# STM8S103_FM1702.net
KiCad netlist of a schematic drawn in Altium Designer
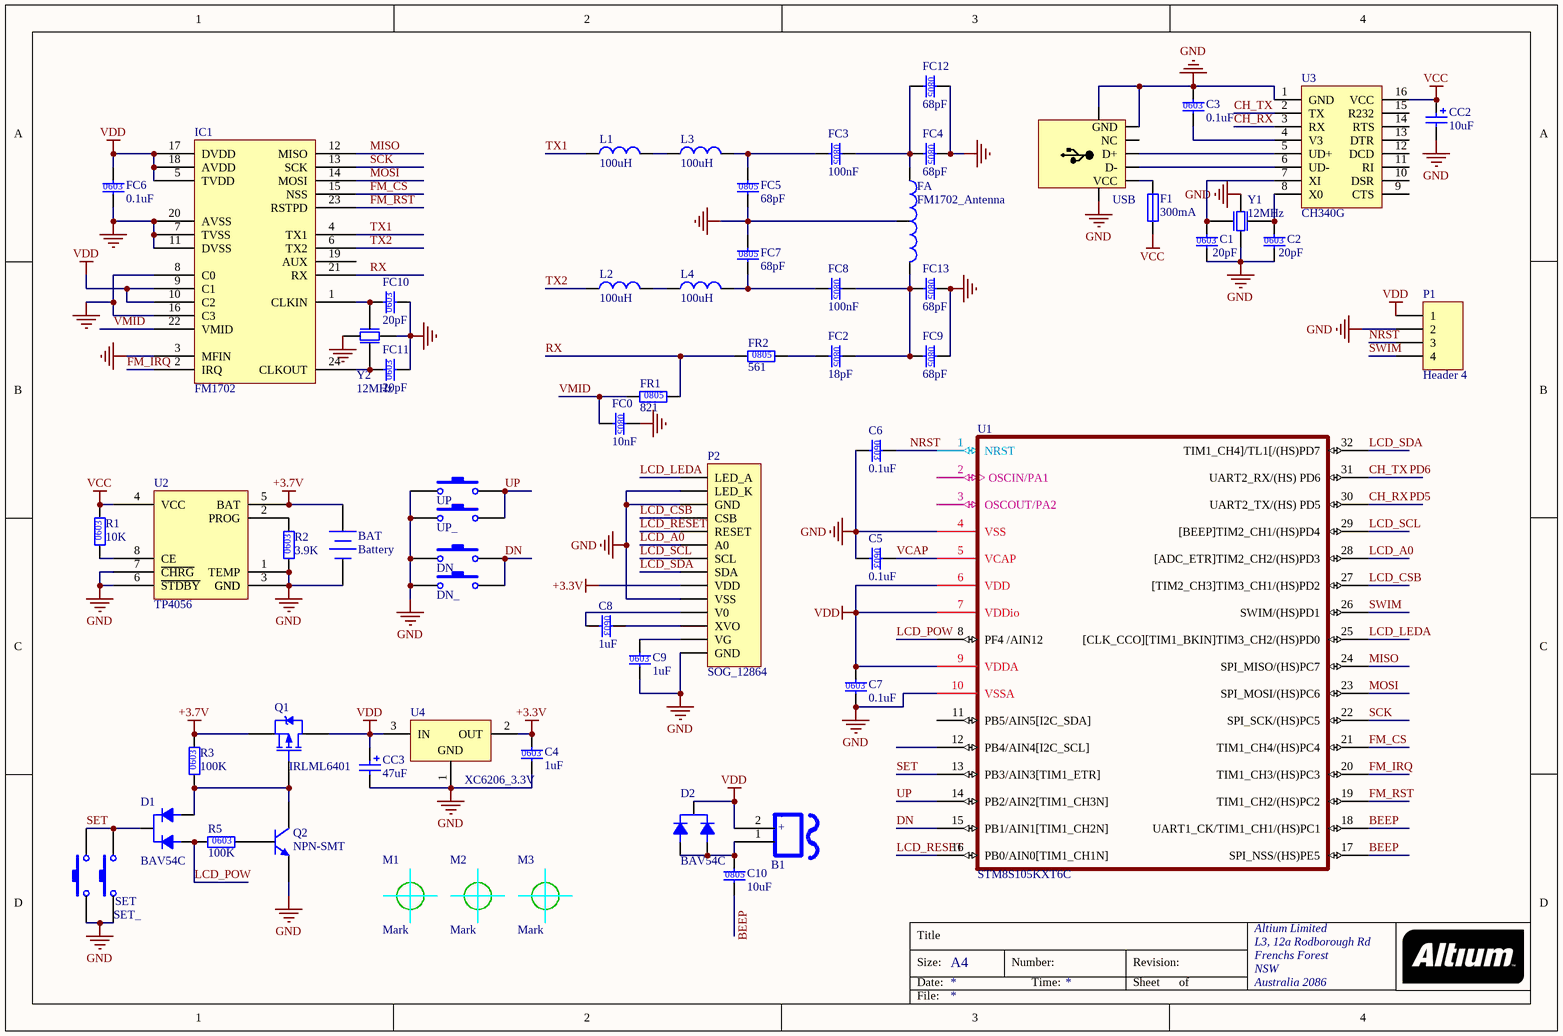
[diagram p0: STM8S103_FM1702.SchDoc]

(export (version "E")
  (design (tool "Eeschema 10.0.6"))
  (components
    (comp (ref "B1")
      (value "BUZZER")
      (footprint "BUZZ_9025")
      (libsource (lib "EButterflySchmeticLibrary") (part "BUZZER"))
    )
    (comp (ref "BAT")
      (value "Battery")
      (footprint "HX1.25-2")
      (description "Multicell Battery")
      (fields (field (name "PUBLISHER") "Altium Limited"))
      (libsource (lib "Altium Designer") (part "Battery-N"))
    )
    (comp (ref "C1")
      (value "20pF")
      (footprint "C0603")
      (description "Polarized Capacitor (Radial)")
      (fields (field (name "Comment") "C0603") (field (name "PUBLISHER") "Altium Limited"))
      (libsource (lib "Capacitance") (part "C0603"))
    )
    (comp (ref "C2")
      (value "20pF")
      (footprint "C0603")
      (description "Polarized Capacitor (Radial)")
      (fields (field (name "Comment") "C0603") (field (name "PUBLISHER") "Altium Limited"))
      (libsource (lib "Capacitance") (part "C0603"))
    )
    (comp (ref "C3")
      (value "0.1uF")
      (footprint "C0603")
      (description "Polarized Capacitor (Radial)")
      (fields (field (name "Comment") "C0603") (field (name "PUBLISHER") "Altium Limited"))
      (libsource (lib "Capacitance") (part "C0603"))
    )
    (comp (ref "C4")
      (value "1uF")
      (footprint "C0603")
      (description "Polarized Capacitor (Radial)")
      (fields (field (name "Comment") "C0603") (field (name "PUBLISHER") "Altium Limited"))
      (libsource (lib "Capacitance") (part "C0603"))
    )
    (comp (ref "C5")
      (value "0.1uF")
      (footprint "C0603")
      (description "Polarized Capacitor (Radial)")
      (fields (field (name "Comment") "C0603") (field (name "PUBLISHER") "Altium Limited"))
      (libsource (lib "Capacitance") (part "C0603"))
    )
    (comp (ref "C6")
      (value "0.1uF")
      (footprint "C0603")
      (description "Polarized Capacitor (Radial)")
      (fields (field (name "Comment") "C0603") (field (name "PUBLISHER") "Altium Limited"))
      (libsource (lib "Capacitance") (part "C0603"))
    )
    (comp (ref "C7")
      (value "0.1uF")
      (footprint "C0603")
      (description "Polarized Capacitor (Radial)")
      (fields (field (name "Comment") "C0603") (field (name "PUBLISHER") "Altium Limited"))
      (libsource (lib "Capacitance") (part "C0603"))
    )
    (comp (ref "C8")
      (value "1uF")
      (footprint "C0603")
      (description "Polarized Capacitor (Radial)")
      (fields (field (name "Comment") "C0603") (field (name "PUBLISHER") "Altium Limited"))
      (libsource (lib "Capacitance") (part "C0603"))
    )
    (comp (ref "C9")
      (value "1uF")
      (footprint "C0603")
      (description "Polarized Capacitor (Radial)")
      (fields (field (name "Comment") "C0603") (field (name "PUBLISHER") "Altium Limited"))
      (libsource (lib "Capacitance") (part "C0603"))
    )
    (comp (ref "C10")
      (value "10uF")
      (footprint "C0805")
      (description "Polarized Capacitor (Radial)")
      (fields (field (name "Comment") "C0805") (field (name "PUBLISHER") "Altium Limited"))
      (libsource (lib "Capacitance") (part "C0805"))
    )
    (comp (ref "CC2")
      (value "Cap Tan B")
      (footprint "TAN-B-3528")
      (description "Polarized Capacitor (Radial)")
      (fields
        (field (name "CAPACITANCE") "10uF")
        (field (name "VOLTAGE") "16V")
        (field (name "PUBLISHER") "Altium Limited")
      )
      (libsource (lib "Capacitance") (part "Cap Tan B"))
    )
    (comp (ref "CC3")
      (value "Cap Tan C")
      (footprint "TAN-C-6032")
      (description "Polarized Capacitor (Radial)")
      (fields
        (field (name "CAPACITANCE") "47uF")
        (field (name "VOLTAGE") "10V")
        (field (name "PUBLISHER") "Altium Limited")
      )
      (libsource (lib "Capacitance") (part "Cap Tan C"))
    )
    (comp (ref "D1")
      (value "BAS40_5")
      (footprint "SOT-23")
      (description "Default Diode")
      (fields (field (name "ALTIUM_UNNAMED_1") "BAV54C") (field (name "PUBLISHER") "Altium Limited"))
      (libsource (lib "Diode") (part "BAS40_5"))
    )
    (comp (ref "D2")
      (value "BAS40_5")
      (footprint "SOT-23")
      (description "Default Diode")
      (fields (field (name "ALTIUM_UNNAMED_1") "BAV54C") (field (name "PUBLISHER") "Altium Limited"))
      (libsource (lib "Diode") (part "BAS40_5"))
    )
    (comp (ref "DN")
      (value "Button")
      (footprint "BUTTON_SMD")
      (fields (field (name "PUBLISHER") "Altium Limited"))
      (libsource (lib "EButterflySchmeticLibrary") (part "Button"))
    )
    (comp (ref "DN_")
      (value "Button")
      (footprint "SWITCH_SMD")
      (fields (field (name "PUBLISHER") "Altium Limited"))
      (libsource (lib "EButterflySchmeticLibrary") (part "Button"))
    )
    (comp (ref "F1")
      (value "300mA")
      (footprint "F1206")
      (description "Fuse")
      (fields (field (name "PUBLISHER") "Altium Limited"))
      (libsource (lib "EButterflySchmeticLibrary") (part "Fuse"))
    )
    (comp (ref "FA")
      (value "FM1702_Antenna")
      (footprint "FM1702_Antenna")
      (libsource (lib "STM8S103_FM1702") (part "FM1702_Antenna"))
    )
    (comp (ref "FC0")
      (value "10nF")
      (footprint "C0805")
      (description "Polarized Capacitor (Radial)")
      (fields (field (name "Comment") "C0805") (field (name "PUBLISHER") "Altium Limited"))
      (libsource (lib "Capacitance") (part "C0805"))
    )
    (comp (ref "FC2")
      (value "18pF")
      (footprint "C0805")
      (description "Polarized Capacitor (Radial)")
      (fields (field (name "Comment") "C0805") (field (name "PUBLISHER") "Altium Limited"))
      (libsource (lib "Capacitance") (part "C0805"))
    )
    (comp (ref "FC3")
      (value "100nF")
      (footprint "C0805")
      (description "Polarized Capacitor (Radial)")
      (fields (field (name "Comment") "C0805") (field (name "PUBLISHER") "Altium Limited"))
      (libsource (lib "Capacitance") (part "C0805"))
    )
    (comp (ref "FC4")
      (value "68pF")
      (footprint "C0805")
      (description "Polarized Capacitor (Radial)")
      (fields (field (name "Comment") "C0805") (field (name "PUBLISHER") "Altium Limited"))
      (libsource (lib "Capacitance") (part "C0805"))
    )
    (comp (ref "FC5")
      (value "68pF")
      (footprint "C0805")
      (description "Polarized Capacitor (Radial)")
      (fields (field (name "Comment") "C0805") (field (name "PUBLISHER") "Altium Limited"))
      (libsource (lib "Capacitance") (part "C0805"))
    )
    (comp (ref "FC6")
      (value "0.1uF")
      (footprint "C0603")
      (description "Polarized Capacitor (Radial)")
      (fields (field (name "Comment") "C0603") (field (name "PUBLISHER") "Altium Limited"))
      (libsource (lib "Capacitance") (part "C0603"))
    )
    (comp (ref "FC7")
      (value "68pF")
      (footprint "C0805")
      (description "Polarized Capacitor (Radial)")
      (fields (field (name "Comment") "C0805") (field (name "PUBLISHER") "Altium Limited"))
      (libsource (lib "Capacitance") (part "C0805"))
    )
    (comp (ref "FC8")
      (value "100nF")
      (footprint "C0805")
      (description "Polarized Capacitor (Radial)")
      (fields (field (name "Comment") "C0805") (field (name "PUBLISHER") "Altium Limited"))
      (libsource (lib "Capacitance") (part "C0805"))
    )
    (comp (ref "FC9")
      (value "68pF")
      (footprint "C0805")
      (description "Polarized Capacitor (Radial)")
      (fields (field (name "Comment") "C0805") (field (name "PUBLISHER") "Altium Limited"))
      (libsource (lib "Capacitance") (part "C0805"))
    )
    (comp (ref "FC10")
      (value "20pF")
      (footprint "C0603")
      (description "Polarized Capacitor (Radial)")
      (fields (field (name "Comment") "C0603") (field (name "PUBLISHER") "Altium Limited"))
      (libsource (lib "Capacitance") (part "C0603"))
    )
    (comp (ref "FC11")
      (value "20pF")
      (footprint "C0603")
      (description "Polarized Capacitor (Radial)")
      (fields (field (name "Comment") "C0603") (field (name "PUBLISHER") "Altium Limited"))
      (libsource (lib "Capacitance") (part "C0603"))
    )
    (comp (ref "FC12")
      (value "68pF")
      (footprint "C0805")
      (description "Polarized Capacitor (Radial)")
      (fields (field (name "Comment") "C0805") (field (name "PUBLISHER") "Altium Limited"))
      (libsource (lib "Capacitance") (part "C0805"))
    )
    (comp (ref "FC13")
      (value "68pF")
      (footprint "C0805")
      (description "Polarized Capacitor (Radial)")
      (fields (field (name "Comment") "C0805") (field (name "PUBLISHER") "Altium Limited"))
      (libsource (lib "Capacitance") (part "C0805"))
    )
    (comp (ref "FR1")
      (value "?")
      (footprint "R0805")
      (fields (field (name "ALTIUM_UNNAMED_1") "821"))
      (libsource (lib "Resistor") (part "R0805"))
    )
    (comp (ref "FR2")
      (value "?")
      (footprint "R0805")
      (fields (field (name "ALTIUM_UNNAMED_1") "561"))
      (libsource (lib "Resistor") (part "R0805"))
    )
    (comp (ref "IC1") (value "FM1702") (footprint "SOP-24L") (libsource (lib "MixedICs") (part "FM1702")))
    (comp (ref "L1")
      (value "100uH")
      (footprint "L2013-0805")
      (description "Inductor")
      (fields (field (name "Comment") "Inductor Chip") (field (name "PUBLISHER") "Altium Limited"))
      (libsource (lib "EButterflySchmeticLibrary") (part "Inductor Chip"))
    )
    (comp (ref "L2")
      (value "100uH")
      (footprint "L2013-0805")
      (description "Inductor")
      (fields (field (name "Comment") "Inductor Chip") (field (name "PUBLISHER") "Altium Limited"))
      (libsource (lib "EButterflySchmeticLibrary") (part "Inductor Chip"))
    )
    (comp (ref "L3")
      (value "100uH")
      (footprint "L2013-0805")
      (description "Inductor")
      (fields (field (name "Comment") "Inductor Chip") (field (name "PUBLISHER") "Altium Limited"))
      (libsource (lib "EButterflySchmeticLibrary") (part "Inductor Chip"))
    )
    (comp (ref "L4")
      (value "100uH")
      (footprint "L2013-0805")
      (description "Inductor")
      (fields (field (name "Comment") "Inductor Chip") (field (name "PUBLISHER") "Altium Limited"))
      (libsource (lib "EButterflySchmeticLibrary") (part "Inductor Chip"))
    )
    (comp (ref "M1")
      (value "Mark")
      (footprint "MARK")
      (fields (field (name "PUBLISHER") "Altium Limited"))
      (libsource (lib "EButterflySchmeticLibrary") (part "Mark"))
    )
    (comp (ref "M2")
      (value "Mark")
      (footprint "MARK")
      (fields (field (name "PUBLISHER") "Altium Limited"))
      (libsource (lib "EButterflySchmeticLibrary") (part "Mark"))
    )
    (comp (ref "M3")
      (value "Mark")
      (footprint "MARK")
      (fields (field (name "PUBLISHER") "Altium Limited"))
      (libsource (lib "EButterflySchmeticLibrary") (part "Mark"))
    )
    (comp (ref "P1")
      (value "Header 4")
      (footprint "HDR1X4")
      (description "Header, 4-Pin")
      (fields (field (name "PUBLISHER") "Altium Limited"))
      (libsource (lib "Connectors") (part "Header 4"))
    )
    (comp (ref "P2")
      (value "SOG_12864")
      (footprint "SOG12864")
      (fields (field (name "PUBLISHER") "Altium Limited"))
      (libsource (lib "Optoelectronic") (part "SOG_12864"))
    )
    (comp (ref "Q1")
      (value "IRLML6401")
      (footprint "SOT-23")
      (description "P-Channel Power MOSFET")
      (fields (field (name "PUBLISHER") "Altium Limited"))
      (libsource (lib "EButterflySchmeticLibrary") (part "IRLML6401"))
    )
    (comp (ref "Q2")
      (value "NPN-SMT")
      (footprint "SO-G3/C2.5")
      (description "NPN Bipolar Transistor")
      (fields (field (name "PUBLISHER") "Altium Limited"))
      (libsource (lib "EButterflySchmeticLibrary") (part "NPN-SMT"))
    )
    (comp (ref "R1")
      (value "?")
      (footprint "R0603")
      (fields (field (name "ALTIUM_UNNAMED_1") "10K"))
      (libsource (lib "Resistor") (part "R0603"))
    )
    (comp (ref "R2")
      (value "?")
      (footprint "R0603")
      (fields (field (name "ALTIUM_UNNAMED_1") "3.9K"))
      (libsource (lib "Resistor") (part "R0603"))
    )
    (comp (ref "R3")
      (value "?")
      (footprint "R0603")
      (fields (field (name "ALTIUM_UNNAMED_1") "100K"))
      (libsource (lib "Resistor") (part "R0603"))
    )
    (comp (ref "R5")
      (value "?")
      (footprint "R0603")
      (fields (field (name "ALTIUM_UNNAMED_1") "100K"))
      (libsource (lib "") (part "R0603_1"))
    )
    (comp (ref "SET")
      (value "Button")
      (footprint "BUTTON_SMD")
      (fields (field (name "PUBLISHER") "Altium Limited"))
      (libsource (lib "EButterflySchmeticLibrary") (part "Button"))
    )
    (comp (ref "SET_")
      (value "Button")
      (footprint "SWITCH_SMD")
      (fields (field (name "PUBLISHER") "Altium Limited"))
      (libsource (lib "EButterflySchmeticLibrary") (part "Button"))
    )
    (comp (ref "U1")
      (value "STM8S105KXT6C")
      (footprint "TQFP-32AN")
      (description "ST 8-bit  Microcontroller")
      (libsource (lib "STM8S") (part "STM8S105K4T6C"))
    )
    (comp (ref "U2") (value "TP4056") (footprint "SOP-8PAD") (libsource (lib "PowerICs") (part "TP4056")))
    (comp (ref "U3") (value "CH340G") (footprint "SOP-16L") (libsource (lib "MixedICs") (part "CH340G")))
    (comp (ref "U4")
      (value "XC6206_3.3V")
      (footprint "SOT-23")
      (description "POSITIVE OUTPUT VOLTAGE")
      (libsource (lib "PowerICs") (part "XC6206"))
    )
    (comp (ref "UP")
      (value "Button")
      (footprint "BUTTON_SMD")
      (fields (field (name "PUBLISHER") "Altium Limited"))
      (libsource (lib "EButterflySchmeticLibrary") (part "Button"))
    )
    (comp (ref "UP_")
      (value "Button")
      (footprint "SWITCH_SMD")
      (fields (field (name "PUBLISHER") "Altium Limited"))
      (libsource (lib "EButterflySchmeticLibrary") (part "Button"))
    )
    (comp (ref "USB") (value "USB") (footprint "USB-B_Micro") (libsource (lib "Connectors") (part "USB")))
    (comp (ref "Y1")
      (value "CRYSTAL")
      (footprint "X3225")
      (description "Crystal Oscillator")
      (fields (field (name "FREQUENCY") "12MHz") (field (name "PUBLISHER") "Altium Limited"))
      (libsource (lib "EButterflySchmeticLibrary") (part "CRYSTAL"))
    )
    (comp (ref "Y2")
      (value "CRYSTAL")
      (footprint "X3225")
      (description "Crystal Oscillator")
      (fields (field (name "FREQUENCY") "12MHz") (field (name "PUBLISHER") "Altium Limited"))
      (libsource (lib "EButterflySchmeticLibrary") (part "CRYSTAL"))
    )
  )
  (nets
    (net (code "1") (name "+3.3V") (class "Default")
      (node (ref "C4") (pin "1") (pinfunction "1_1") (pintype "passive"))
      (node (ref "P2") (pin "9") (pinfunction "VDD_9") (pintype "passive"))
      (node (ref "U4") (pin "2") (pinfunction "OUT_2") (pintype "power_in"))
    )
    (net (code "2") (name "+3.7V") (class "Default")
      (node (ref "BAT") (pin "2") (pinfunction "+_2") (pintype "passive"))
      (node (ref "Q1") (pin "2") (pinfunction "S_2") (pintype "passive"))
      (node (ref "R3") (pin "2") (pinfunction "2_2") (pintype "passive"))
      (node (ref "U2") (pin "5") (pinfunction "BAT_5") (pintype "passive"))
    )
    (net (code "3") (name "/BEEP") (class "Default")
      (node (ref "C10") (pin "2") (pinfunction "2_2") (pintype "passive"))
      (node (ref "U1") (pin "17") (pinfunction "SPI_NSS/(HS)PE5_17") (pintype "bidirectional"))
      (node (ref "U1") (pin "18") (pinfunction "UART1_CK/TIM1_CH1/(HS)PC1_18") (pintype "bidirectional"))
    )
    (net (code "4") (name "/CH_RX") (class "Default")
      (node (ref "U1") (pin "30") (pinfunction "UART2_TX/(HS)_PD5_30") (pintype "bidirectional"))
      (node (ref "U3") (pin "3") (pinfunction "RX_3") (pintype "passive"))
    )
    (net (code "5") (name "/CH_TX") (class "Default")
      (node (ref "U1") (pin "31") (pinfunction "UART2_RX/(HS)_PD6_31") (pintype "bidirectional"))
      (node (ref "U3") (pin "2") (pinfunction "TX_2") (pintype "passive"))
    )
    (net (code "6") (name "/DN") (class "Default")
      (node (ref "DN") (pin "2") (pinfunction "2_2") (pintype "passive"))
      (node (ref "DN_") (pin "2") (pinfunction "2_2") (pintype "passive"))
      (node (ref "U1") (pin "15") (pinfunction "PB1/AIN1[TIM1_CH2N]_15") (pintype "bidirectional"))
    )
    (net (code "7") (name "/FM_CS") (class "Default")
      (node (ref "IC1") (pin "15") (pinfunction "NSS_15") (pintype "passive"))
      (node (ref "U1") (pin "21") (pinfunction "TIM1_CH4/(HS)PC4_21") (pintype "bidirectional"))
    )
    (net (code "8") (name "/FM_IRQ") (class "Default")
      (node (ref "IC1") (pin "2") (pinfunction "IRQ_2") (pintype "passive"))
      (node (ref "U1") (pin "20") (pinfunction "TIM1_CH3/(HS)PC3_20") (pintype "bidirectional"))
    )
    (net (code "9") (name "/FM_RST") (class "Default")
      (node (ref "IC1") (pin "23") (pinfunction "RSTPD_23") (pintype "passive"))
      (node (ref "U1") (pin "19") (pinfunction "TIM1_CH2/(HS)PC2_19") (pintype "bidirectional"))
    )
    (net (code "10") (name "/LCD_A0") (class "Default")
      (node (ref "P2") (pin "6") (pinfunction "A0_6") (pintype "passive"))
      (node (ref "U1") (pin "28") (pinfunction "[ADC_ETR]TIM2_CH2/(HS)PD3_28") (pintype "bidirectional"))
    )
    (net (code "11") (name "/LCD_CSB") (class "Default")
      (node (ref "P2") (pin "4") (pinfunction "CSB_4") (pintype "passive"))
      (node (ref "U1") (pin "27") (pinfunction "[TIM2_CH3]TIM3_CH1/(HS)PD2_27") (pintype "bidirectional"))
    )
    (net (code "12") (name "/LCD_LEDA") (class "Default")
      (node (ref "P2") (pin "1") (pinfunction "LED_A_1") (pintype "passive"))
      (node (ref "U1") (pin "25") (pinfunction "[CLK_CCO][TIM1_BKIN]TIM3_CH2/(HS)PD0_25") (pintype "bidirectional"))
    )
    (net (code "13") (name "/LCD_POW") (class "Default")
      (node (ref "D1") (pin "1") (pintype "passive"))
      (node (ref "R5") (pin "1") (pinfunction "1_1") (pintype "passive"))
      (node (ref "U1") (pin "8") (pinfunction "PF4_/AIN12_8") (pintype "bidirectional"))
    )
    (net (code "14") (name "/LCD_RESET") (class "Default")
      (node (ref "P2") (pin "5") (pinfunction "RESET_5") (pintype "passive"))
      (node (ref "U1") (pin "16") (pinfunction "PB0/AIN0[TIM1_CH1N]_16") (pintype "bidirectional"))
    )
    (net (code "15") (name "/LCD_SCL") (class "Default")
      (node (ref "P2") (pin "7") (pinfunction "SCL_7") (pintype "passive"))
      (node (ref "U1") (pin "29") (pinfunction "[BEEP]TIM2_CH1/(HS)PD4_29") (pintype "bidirectional"))
    )
    (net (code "16") (name "/LCD_SDA") (class "Default")
      (node (ref "P2") (pin "8") (pinfunction "SDA_8") (pintype "passive"))
      (node (ref "U1") (pin "32") (pinfunction "TIM1_CH4]/TL1[/(HS)PD7_32") (pintype "bidirectional"))
    )
    (net (code "17") (name "/MISO") (class "Default")
      (node (ref "IC1") (pin "12") (pinfunction "MISO_12") (pintype "passive"))
      (node (ref "U1") (pin "24") (pinfunction "SPI_MISO/(HS)PC7_24") (pintype "bidirectional"))
    )
    (net (code "18") (name "/MOSI") (class "Default")
      (node (ref "IC1") (pin "14") (pinfunction "MOSI_14") (pintype "passive"))
      (node (ref "U1") (pin "23") (pinfunction "SPI_MOSI/(HS)PC6_23") (pintype "bidirectional"))
    )
    (net (code "19") (name "/NRST") (class "Default")
      (node (ref "C6") (pin "1") (pinfunction "1_1") (pintype "passive"))
      (node (ref "P1") (pin "3") (pinfunction "3_3") (pintype "passive"))
      (node (ref "U1") (pin "1") (pinfunction "NRST_1") (pintype "bidirectional"))
    )
    (net (code "20") (name "/RX") (class "Default")
      (node (ref "FR1") (pin "2") (pinfunction "2_2") (pintype "passive"))
      (node (ref "FR2") (pin "1") (pinfunction "1_1") (pintype "passive"))
      (node (ref "IC1") (pin "21") (pinfunction "RX_21") (pintype "passive"))
    )
    (net (code "21") (name "/SCK") (class "Default")
      (node (ref "IC1") (pin "13") (pinfunction "SCK_13") (pintype "passive"))
      (node (ref "U1") (pin "22") (pinfunction "SPI_SCK/(HS)PC5_22") (pintype "bidirectional"))
    )
    (net (code "22") (name "/SET") (class "Default")
      (node (ref "D1") (pin "3") (pintype "passive"))
      (node (ref "SET") (pin "2") (pinfunction "2_2") (pintype "passive"))
      (node (ref "SET_") (pin "2") (pinfunction "2_2") (pintype "passive"))
      (node (ref "U1") (pin "13") (pinfunction "PB3/AIN3[TIM1_ETR]_13") (pintype "bidirectional"))
    )
    (net (code "23") (name "/SWIM") (class "Default")
      (node (ref "P1") (pin "4") (pinfunction "4_4") (pintype "passive"))
      (node (ref "U1") (pin "26") (pinfunction "SWIM/(HS)PD1_26") (pintype "bidirectional"))
    )
    (net (code "24") (name "/TX1") (class "Default")
      (node (ref "IC1") (pin "4") (pinfunction "TX1_4") (pintype "passive"))
      (node (ref "L1") (pin "1") (pinfunction "1_1") (pintype "passive"))
    )
    (net (code "25") (name "/TX2") (class "Default")
      (node (ref "IC1") (pin "6") (pinfunction "TX2_6") (pintype "passive"))
      (node (ref "L2") (pin "1") (pinfunction "1_1") (pintype "passive"))
    )
    (net (code "26") (name "/UP") (class "Default")
      (node (ref "U1") (pin "14") (pinfunction "PB2/AIN2[TIM1_CH3N]_14") (pintype "bidirectional"))
      (node (ref "UP") (pin "2") (pinfunction "2_2") (pintype "passive"))
      (node (ref "UP_") (pin "2") (pinfunction "2_2") (pintype "passive"))
    )
    (net (code "27") (name "/VCAP") (class "Default")
      (node (ref "C5") (pin "1") (pinfunction "1_1") (pintype "passive"))
      (node (ref "U1") (pin "5") (pinfunction "VCAP_5") (pintype "power_in"))
    )
    (net (code "28") (name "/VMID") (class "Default")
      (node (ref "FC0") (pin "2") (pinfunction "2_2") (pintype "passive"))
      (node (ref "FR1") (pin "1") (pinfunction "1_1") (pintype "passive"))
      (node (ref "IC1") (pin "22") (pinfunction "VMID_22") (pintype "passive"))
    )
    (net (code "29") (name "GND") (class "Default")
      (node (ref "BAT") (pin "1") (pinfunction "-_1") (pintype "passive"))
      (node (ref "C1") (pin "2") (pinfunction "2_2") (pintype "passive"))
      (node (ref "C2") (pin "2") (pinfunction "2_2") (pintype "passive"))
      (node (ref "C3") (pin "1") (pinfunction "1_1") (pintype "passive"))
      (node (ref "C4") (pin "2") (pinfunction "2_2") (pintype "passive"))
      (node (ref "C5") (pin "2") (pinfunction "2_2") (pintype "passive"))
      (node (ref "C6") (pin "2") (pinfunction "2_2") (pintype "passive"))
      (node (ref "C7") (pin "2") (pinfunction "2_2") (pintype "passive"))
      (node (ref "C9") (pin "2") (pinfunction "2_2") (pintype "passive"))
      (node (ref "CC2") (pin "1") (pinfunction "2_1") (pintype "passive"))
      (node (ref "CC3") (pin "1") (pinfunction "2_1") (pintype "passive"))
      (node (ref "DN") (pin "1") (pinfunction "1_1") (pintype "passive"))
      (node (ref "DN_") (pin "1") (pinfunction "1_1") (pintype "passive"))
      (node (ref "FA") (pin "2") (pinfunction "2_2") (pintype "passive"))
      (node (ref "FC0") (pin "1") (pinfunction "1_1") (pintype "passive"))
      (node (ref "FC10") (pin "2") (pinfunction "2_2") (pintype "passive"))
      (node (ref "FC11") (pin "2") (pinfunction "2_2") (pintype "passive"))
      (node (ref "FC12") (pin "1") (pinfunction "1_1") (pintype "passive"))
      (node (ref "FC13") (pin "1") (pinfunction "1_1") (pintype "passive"))
      (node (ref "FC4") (pin "1") (pinfunction "1_1") (pintype "passive"))
      (node (ref "FC5") (pin "2") (pinfunction "2_2") (pintype "passive"))
      (node (ref "FC6") (pin "2") (pinfunction "2_2") (pintype "passive"))
      (node (ref "FC7") (pin "1") (pinfunction "1_1") (pintype "passive"))
      (node (ref "FC9") (pin "1") (pinfunction "1_1") (pintype "passive"))
      (node (ref "IC1") (pin "11") (pinfunction "DVSS_11") (pintype "passive"))
      (node (ref "IC1") (pin "16") (pinfunction "C3_16") (pintype "passive"))
      (node (ref "IC1") (pin "20") (pinfunction "AVSS_20") (pintype "passive"))
      (node (ref "IC1") (pin "3") (pinfunction "MFIN_3") (pintype "passive"))
      (node (ref "IC1") (pin "7") (pinfunction "TVSS_7") (pintype "passive"))
      (node (ref "IC1") (pin "8") (pinfunction "C0_8") (pintype "passive"))
      (node (ref "P1") (pin "2") (pinfunction "2_2") (pintype "passive"))
      (node (ref "P2") (pin "10") (pinfunction "VSS_10") (pintype "passive"))
      (node (ref "P2") (pin "14") (pinfunction "GND_14") (pintype "passive"))
      (node (ref "P2") (pin "2") (pinfunction "LED_K_2") (pintype "passive"))
      (node (ref "P2") (pin "3") (pinfunction "GND_3") (pintype "passive"))
      (node (ref "Q2") (pin "1") (pinfunction "E_1") (pintype "passive"))
      (node (ref "R2") (pin "1") (pinfunction "1_1") (pintype "passive"))
      (node (ref "SET") (pin "1") (pinfunction "1_1") (pintype "passive"))
      (node (ref "SET_") (pin "1") (pinfunction "1_1") (pintype "passive"))
      (node (ref "U1") (pin "10") (pinfunction "VSSA_10") (pintype "power_in"))
      (node (ref "U1") (pin "4") (pinfunction "VSS_4") (pintype "power_in"))
      (node (ref "U2") (pin "1") (pinfunction "TEMP_1") (pintype "passive"))
      (node (ref "U2") (pin "3") (pinfunction "GND_3") (pintype "passive"))
      (node (ref "U2") (pin "6") (pinfunction "STDBY_6") (pintype "passive"))
      (node (ref "U2") (pin "7") (pinfunction "CHRG_7") (pintype "passive"))
      (node (ref "U2") (pin "9") (pinfunction "GND_9") (pintype "passive"))
      (node (ref "U3") (pin "1") (pinfunction "GND_1") (pintype "passive"))
      (node (ref "U4") (pin "1") (pinfunction "GND_1") (pintype "power_in"))
      (node (ref "UP") (pin "1") (pinfunction "1_1") (pintype "passive"))
      (node (ref "UP_") (pin "1") (pinfunction "1_1") (pintype "passive"))
      (node (ref "USB") (pin "5") (pinfunction "GND_5") (pintype "passive"))
      (node (ref "USB") (pin "6") (pinfunction "GND_6") (pintype "passive"))
      (node (ref "USB") (pin "7") (pinfunction "GND_7") (pintype "passive"))
      (node (ref "Y1") (pin "2") (pinfunction "GND_2") (pintype "passive"))
      (node (ref "Y1") (pin "4") (pinfunction "GND_4") (pintype "passive"))
      (node (ref "Y2") (pin "2") (pinfunction "GND_2") (pintype "passive"))
      (node (ref "Y2") (pin "4") (pinfunction "GND_4") (pintype "passive"))
    )
    (net (code "30") (name "Net-(B1-Pad1)") (class "Default")
      (node (ref "B1") (pin "1") (pinfunction "1_1") (pintype "passive"))
      (node (ref "C10") (pin "1") (pinfunction "1_1") (pintype "passive"))
      (node (ref "D2") (pin "1") (pintype "passive"))
      (node (ref "D2") (pin "2") (pintype "passive"))
    )
    (net (code "31") (name "Net-(FA-Pad1)") (class "Default")
      (node (ref "FA") (pin "1") (pinfunction "1_1") (pintype "passive"))
      (node (ref "FC12") (pin "2") (pinfunction "2_2") (pintype "passive"))
      (node (ref "FC3") (pin "1") (pinfunction "1_1") (pintype "passive"))
      (node (ref "FC4") (pin "2") (pinfunction "2_2") (pintype "passive"))
    )
    (net (code "32") (name "Net-(FA-Pad3)") (class "Default")
      (node (ref "FA") (pin "3") (pinfunction "3_3") (pintype "passive"))
      (node (ref "FC13") (pin "2") (pinfunction "2_2") (pintype "passive"))
      (node (ref "FC2") (pin "1") (pinfunction "1_1") (pintype "passive"))
      (node (ref "FC8") (pin "1") (pinfunction "1_1") (pintype "passive"))
      (node (ref "FC9") (pin "2") (pinfunction "2_2") (pintype "passive"))
    )
    (net (code "33") (name "Net-(FC2-Pad2)") (class "Default")
      (node (ref "FC2") (pin "2") (pinfunction "2_2") (pintype "passive"))
      (node (ref "FR2") (pin "2") (pinfunction "2_2") (pintype "passive"))
    )
    (net (code "34") (name "Net-(FC3-Pad2)") (class "Default")
      (node (ref "FC3") (pin "2") (pinfunction "2_2") (pintype "passive"))
      (node (ref "FC5") (pin "1") (pinfunction "1_1") (pintype "passive"))
      (node (ref "L3") (pin "2") (pinfunction "2_2") (pintype "passive"))
    )
    (net (code "35") (name "Net-(FC7-Pad2)") (class "Default")
      (node (ref "FC7") (pin "2") (pinfunction "2_2") (pintype "passive"))
      (node (ref "FC8") (pin "2") (pinfunction "2_2") (pintype "passive"))
      (node (ref "L4") (pin "2") (pinfunction "2_2") (pintype "passive"))
    )
    (net (code "36") (name "Net-(IC1-CLKIN)") (class "Default")
      (node (ref "FC10") (pin "1") (pinfunction "1_1") (pintype "passive"))
      (node (ref "IC1") (pin "1") (pinfunction "CLKIN_1") (pintype "passive"))
      (node (ref "Y2") (pin "1") (pinfunction "OSC1_1") (pintype "passive"))
    )
    (net (code "37") (name "Net-(IC1-CLKOUT)") (class "Default")
      (node (ref "FC11") (pin "1") (pinfunction "1_1") (pintype "passive"))
      (node (ref "IC1") (pin "24") (pinfunction "CLKOUT_24") (pintype "passive"))
      (node (ref "Y2") (pin "3") (pinfunction "OSC2_3") (pintype "passive"))
    )
    (net (code "38") (name "Net-(L1-Pad2)") (class "Default")
      (node (ref "L1") (pin "2") (pinfunction "2_2") (pintype "passive"))
      (node (ref "L3") (pin "1") (pinfunction "1_1") (pintype "passive"))
    )
    (net (code "39") (name "Net-(L2-Pad2)") (class "Default")
      (node (ref "L2") (pin "2") (pinfunction "2_2") (pintype "passive"))
      (node (ref "L4") (pin "1") (pinfunction "1_1") (pintype "passive"))
    )
    (net (code "40") (name "Net-(P2-V0)") (class "Default")
      (node (ref "C8") (pin "2") (pinfunction "2_2") (pintype "passive"))
      (node (ref "P2") (pin "11") (pinfunction "V0_11") (pintype "passive"))
    )
    (net (code "41") (name "Net-(P2-VG)") (class "Default")
      (node (ref "C9") (pin "1") (pinfunction "1_1") (pintype "passive"))
      (node (ref "P2") (pin "13") (pinfunction "VG_13") (pintype "passive"))
    )
    (net (code "42") (name "Net-(P2-XVO)") (class "Default")
      (node (ref "C8") (pin "1") (pinfunction "1_1") (pintype "passive"))
      (node (ref "P2") (pin "12") (pinfunction "XVO_12") (pintype "passive"))
    )
    (net (code "43") (name "Net-(Q1-G)") (class "Default")
      (node (ref "D1") (pin "2") (pintype "passive"))
      (node (ref "Q1") (pin "1") (pinfunction "G_1") (pintype "passive"))
      (node (ref "Q2") (pin "3") (pinfunction "C_3") (pintype "passive"))
      (node (ref "R3") (pin "1") (pinfunction "1_1") (pintype "passive"))
    )
    (net (code "44") (name "Net-(Q2-B)") (class "Default")
      (node (ref "Q2") (pin "2") (pinfunction "B_2") (pintype "passive"))
      (node (ref "R5") (pin "2") (pinfunction "2_2") (pintype "passive"))
    )
    (net (code "45") (name "Net-(U2-CE)") (class "Default")
      (node (ref "R1") (pin "1") (pinfunction "1_1") (pintype "passive"))
      (node (ref "U2") (pin "8") (pinfunction "CE_8") (pintype "passive"))
    )
    (net (code "46") (name "Net-(U2-PROG)") (class "Default")
      (node (ref "R2") (pin "2") (pinfunction "2_2") (pintype "passive"))
      (node (ref "U2") (pin "2") (pinfunction "PROG_2") (pintype "passive"))
    )
    (net (code "47") (name "Net-(U3-UD+)") (class "Default")
      (node (ref "U3") (pin "5") (pinfunction "UD+_5") (pintype "passive"))
      (node (ref "USB") (pin "3") (pinfunction "D+_3") (pintype "passive"))
    )
    (net (code "48") (name "Net-(U3-UD-)") (class "Default")
      (node (ref "U3") (pin "6") (pinfunction "UD-_6") (pintype "passive"))
      (node (ref "USB") (pin "2") (pinfunction "D-_2") (pintype "passive"))
    )
    (net (code "49") (name "Net-(U3-V3)") (class "Default")
      (node (ref "C3") (pin "2") (pinfunction "2_2") (pintype "passive"))
      (node (ref "U3") (pin "4") (pinfunction "V3_4") (pintype "passive"))
    )
    (net (code "50") (name "Net-(U3-X0)") (class "Default")
      (node (ref "C2") (pin "1") (pinfunction "1_1") (pintype "passive"))
      (node (ref "U3") (pin "8") (pinfunction "X0_8") (pintype "passive"))
      (node (ref "Y1") (pin "1") (pinfunction "OSC1_1") (pintype "passive"))
    )
    (net (code "51") (name "Net-(U3-XI)") (class "Default")
      (node (ref "C1") (pin "1") (pinfunction "1_1") (pintype "passive"))
      (node (ref "U3") (pin "7") (pinfunction "XI_7") (pintype "passive"))
      (node (ref "Y1") (pin "3") (pinfunction "OSC2_3") (pintype "passive"))
    )
    (net (code "52") (name "Net-(USB-VCC)") (class "Default")
      (node (ref "F1") (pin "1") (pinfunction "1_1") (pintype "passive"))
      (node (ref "USB") (pin "1") (pinfunction "VCC_1") (pintype "passive"))
    )
    (net (code "53") (name "VCC") (class "Default")
      (node (ref "CC2") (pin "2") (pinfunction "1_2") (pintype "passive"))
      (node (ref "F1") (pin "2") (pinfunction "2_2") (pintype "passive"))
      (node (ref "R1") (pin "2") (pinfunction "2_2") (pintype "passive"))
      (node (ref "U2") (pin "4") (pinfunction "VCC_4") (pintype "passive"))
      (node (ref "U3") (pin "16") (pinfunction "VCC_16") (pintype "passive"))
    )
    (net (code "54") (name "VDD") (class "Default")
      (node (ref "B1") (pin "2") (pinfunction "2_2") (pintype "passive"))
      (node (ref "C7") (pin "1") (pinfunction "1_1") (pintype "passive"))
      (node (ref "CC3") (pin "2") (pinfunction "1_2") (pintype "passive"))
      (node (ref "D2") (pin "3") (pintype "passive"))
      (node (ref "FC6") (pin "1") (pinfunction "1_1") (pintype "passive"))
      (node (ref "IC1") (pin "10") (pinfunction "C2_10") (pintype "passive"))
      (node (ref "IC1") (pin "17") (pinfunction "DVDD_17") (pintype "passive"))
      (node (ref "IC1") (pin "18") (pinfunction "AVDD_18") (pintype "passive"))
      (node (ref "IC1") (pin "5") (pinfunction "TVDD_5") (pintype "passive"))
      (node (ref "IC1") (pin "9") (pinfunction "C1_9") (pintype "passive"))
      (node (ref "P1") (pin "1") (pinfunction "1_1") (pintype "passive"))
      (node (ref "Q1") (pin "3") (pinfunction "D_3") (pintype "passive"))
      (node (ref "U1") (pin "6") (pinfunction "VDD_6") (pintype "power_in"))
      (node (ref "U1") (pin "7") (pinfunction "VDDio_7") (pintype "power_in"))
      (node (ref "U1") (pin "9") (pinfunction "VDDA_9") (pintype "power_in"))
      (node (ref "U4") (pin "3") (pinfunction "IN_3") (pintype "power_in"))
    )
    (net (code "55") (name "unconnected-(IC1-AUX-Pad19)") (class "Default")
      (node (ref "IC1") (pin "19") (pinfunction "AUX_19") (pintype "passive"))
    )
    (net (code "56") (name "unconnected-(U1-OSCIN{slash}PA1-Pad2)") (class "Default")
      (node (ref "U1") (pin "2") (pinfunction "OSCIN/PA1_2") (pintype "bidirectional"))
    )
    (net (code "57") (name "unconnected-(U1-OSCOUT{slash}PA2-Pad3)") (class "Default")
      (node (ref "U1") (pin "3") (pinfunction "OSCOUT/PA2_3") (pintype "bidirectional"))
    )
    (net (code "58") (name "unconnected-(U1-PB4{slash}AIN4[I2C_SCL]-Pad12)") (class "Default")
      (node (ref "U1") (pin "12") (pinfunction "PB4/AIN4[I2C_SCL]_12") (pintype "bidirectional"))
    )
    (net (code "59") (name "unconnected-(U1-PB5{slash}AIN5[I2C_SDA]-Pad11)") (class "Default")
      (node (ref "U1") (pin "11") (pinfunction "PB5/AIN5[I2C_SDA]_11") (pintype "bidirectional"))
    )
    (net (code "60") (name "unconnected-(U3-CTS-Pad9)") (class "Default")
      (node (ref "U3") (pin "9") (pinfunction "CTS_9") (pintype "passive"))
    )
    (net (code "61") (name "unconnected-(U3-DCD-Pad12)") (class "Default")
      (node (ref "U3") (pin "12") (pinfunction "DCD_12") (pintype "passive"))
    )
    (net (code "62") (name "unconnected-(U3-DSR-Pad10)") (class "Default")
      (node (ref "U3") (pin "10") (pinfunction "DSR_10") (pintype "passive"))
    )
    (net (code "63") (name "unconnected-(U3-DTR-Pad13)") (class "Default")
      (node (ref "U3") (pin "13") (pinfunction "DTR_13") (pintype "passive"))
    )
    (net (code "64") (name "unconnected-(U3-R232-Pad15)") (class "Default")
      (node (ref "U3") (pin "15") (pinfunction "R232_15") (pintype "passive"))
    )
    (net (code "65") (name "unconnected-(U3-RI-Pad11)") (class "Default")
      (node (ref "U3") (pin "11") (pinfunction "RI_11") (pintype "passive"))
    )
    (net (code "66") (name "unconnected-(U3-RTS-Pad14)") (class "Default")
      (node (ref "U3") (pin "14") (pinfunction "RTS_14") (pintype "passive"))
    )
    (net (code "67") (name "unconnected-(USB-NC-Pad4)") (class "Default")
      (node (ref "USB") (pin "4") (pinfunction "NC_4") (pintype "passive"))
    )
  )
)
